# working.net
KiCad netlist of a schematic drawn in EAGLE
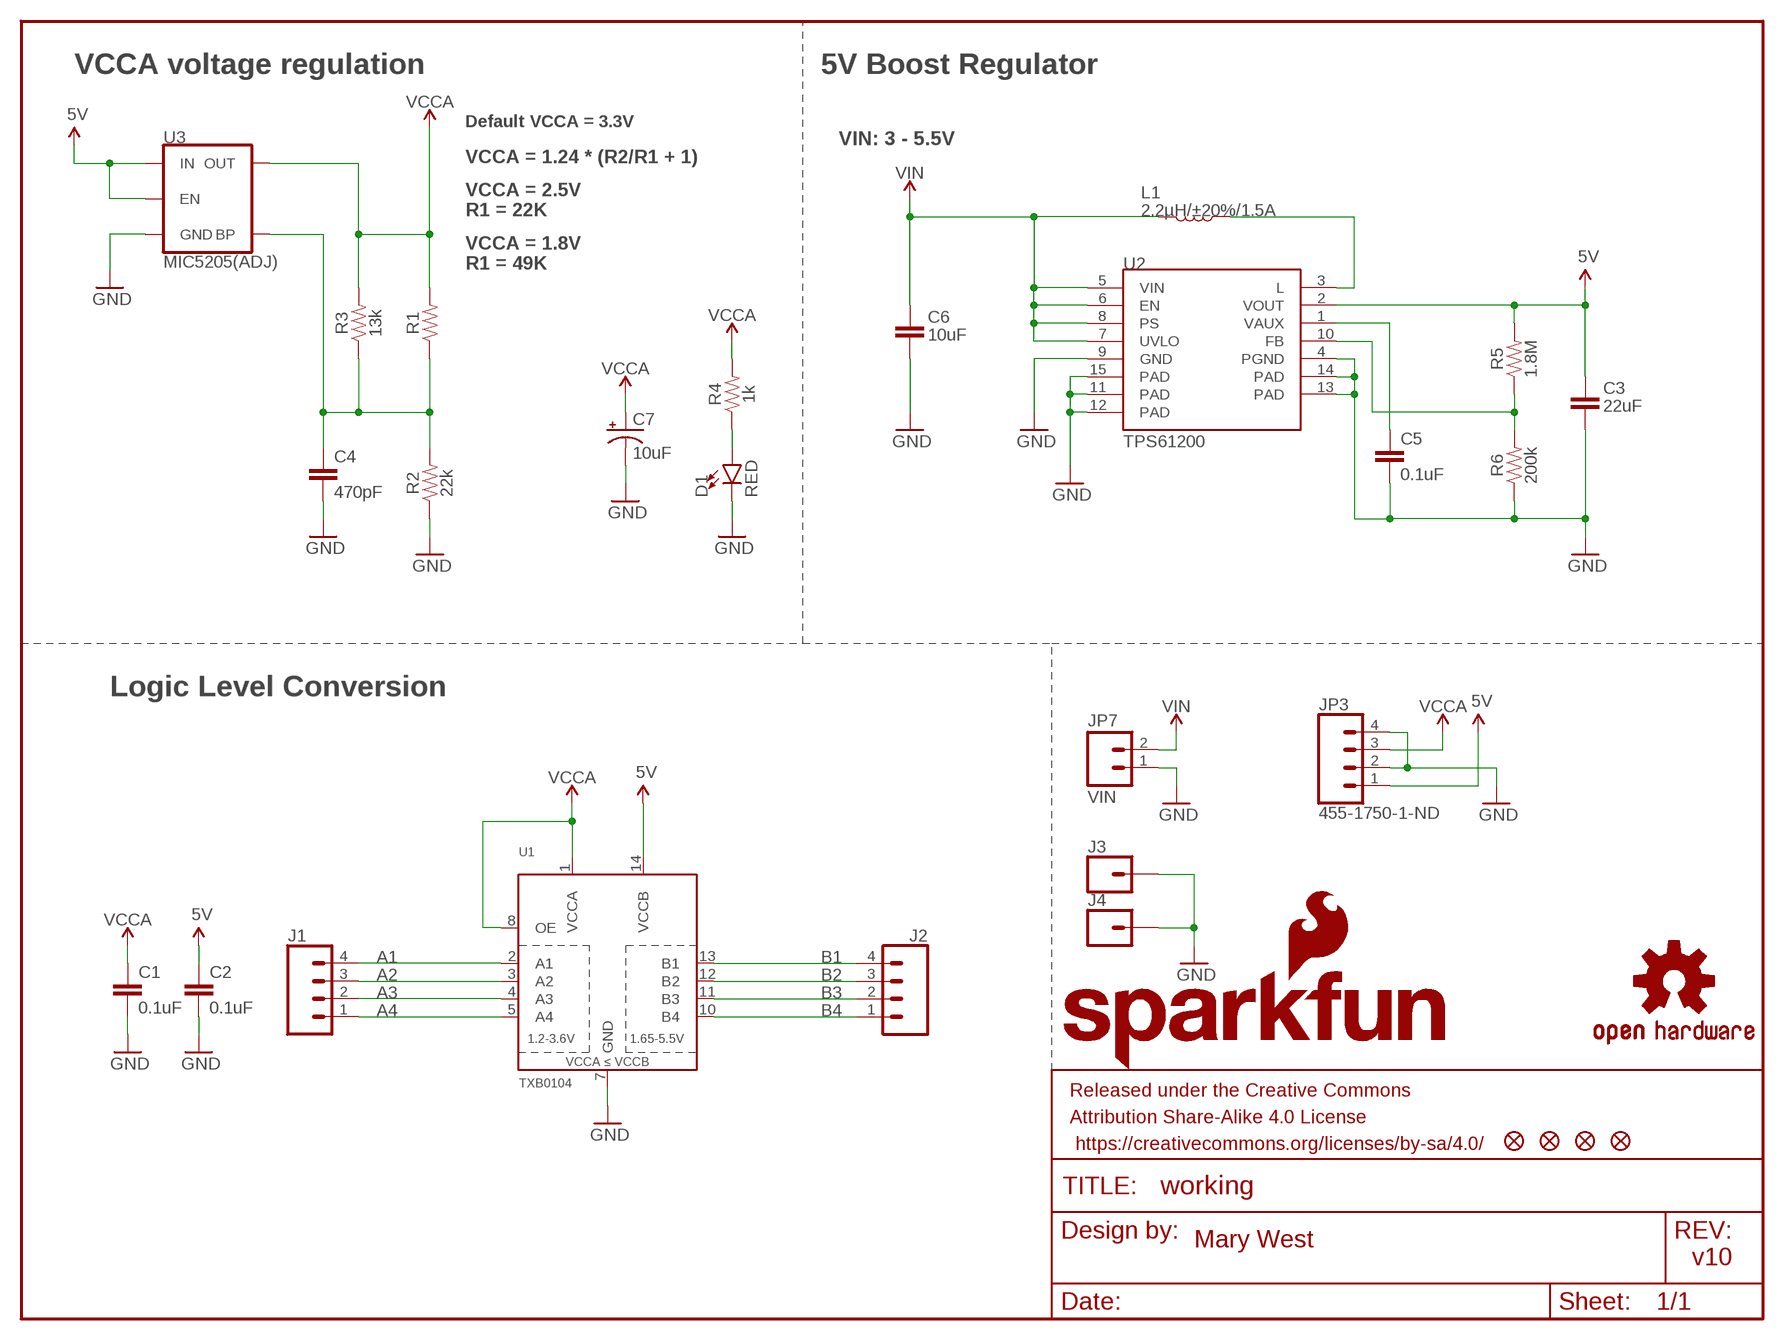
[diagram p0: schematic, sheet 1]

(export (version "E")
  (design (tool "Eeschema 10.0.6"))
  (components
    (comp (ref "C1")
      (value "0.1uF")
      (footprint "eagle-import:0603-CAP")
      (libsource (lib "eagle-import") (part "0.1UF-25V(+80/-20%)(0603)"))
    )
    (comp (ref "C2")
      (value "0.1uF")
      (footprint "eagle-import:0603-CAP")
      (libsource (lib "eagle-import") (part "0.1UF-25V(+80/-20%)(0603)"))
    )
    (comp (ref "C3")
      (value "22uF")
      (footprint "eagle-import:0805")
      (libsource (lib "eagle-import") (part "22UF-0805-6.3V-20%"))
    )
    (comp (ref "C4")
      (value "470pF")
      (footprint "eagle-import:0603")
      (libsource (lib "eagle-import") (part "470PF-0603-50V-5%"))
    )
    (comp (ref "C5")
      (value "0.1uF")
      (footprint "eagle-import:0603")
      (libsource (lib "eagle-import") (part "0.1UF-0603-25V-(+80/-20%)"))
    )
    (comp (ref "C6")
      (value "10uF")
      (footprint "eagle-import:0603")
      (libsource (lib "eagle-import") (part "10UF-0603-6.3V-20%"))
    )
    (comp (ref "C7")
      (value "10uF")
      (footprint "eagle-import:EIA3216")
      (libsource (lib "eagle-import") (part "10UF-POLAR-EIA3216-16V-10%(TANT)"))
    )
    (comp (ref "D1")
      (value "RED")
      (footprint "eagle-import:LED-0603")
      (libsource (lib "eagle-import") (part "LED-RED0603"))
    )
    (comp (ref "FD1")
      (value "FIDUCIALUFIDUCIAL")
      (footprint "eagle-import:FIDUCIAL-MICRO")
      (libsource (lib "eagle-import") (part "FIDUCIALUFIDUCIAL"))
    )
    (comp (ref "FD2")
      (value "FIDUCIALUFIDUCIAL")
      (footprint "eagle-import:FIDUCIAL-MICRO")
      (libsource (lib "eagle-import") (part "FIDUCIALUFIDUCIAL"))
    )
    (comp (ref "FD3")
      (value "FIDUCIALUFIDUCIAL")
      (footprint "eagle-import:FIDUCIAL-MICRO")
      (libsource (lib "eagle-import") (part "FIDUCIALUFIDUCIAL"))
    )
    (comp (ref "FD4")
      (value "FIDUCIALUFIDUCIAL")
      (footprint "eagle-import:FIDUCIAL-MICRO")
      (libsource (lib "eagle-import") (part "FIDUCIALUFIDUCIAL"))
    )
    (comp (ref "FRAME1")
      (value "FRAME-LETTER")
      (footprint "eagle-import:CREATIVE_COMMONS")
      (libsource (lib "eagle-import") (part "FRAME-LETTER"))
    )
    (comp (ref "J1")
      (value "CONN_04")
      (footprint "eagle-import:1X04")
      (libsource (lib "eagle-import") (part "CONN_04"))
    )
    (comp (ref "J2")
      (value "CONN_04")
      (footprint "eagle-import:1X04")
      (libsource (lib "eagle-import") (part "CONN_04"))
    )
    (comp (ref "J3")
      (value "CONN_01")
      (footprint "eagle-import:1X01")
      (libsource (lib "eagle-import") (part "CONN_01"))
    )
    (comp (ref "J4")
      (value "CONN_01")
      (footprint "eagle-import:1X01")
      (libsource (lib "eagle-import") (part "CONN_01"))
    )
    (comp (ref "JP3")
      (value "455-1750-1-ND")
      (footprint "eagle-import:1X04")
      (libsource (lib "eagle-import") (part "CONN_04"))
    )
    (comp (ref "JP7")
      (value "VIN")
      (footprint "eagle-import:1X02")
      (libsource (lib "eagle-import") (part "M02PTH"))
    )
    (comp (ref "L1")
      (value "2.2µH/±20%/1.5A")
      (footprint "eagle-import:INDUCTOR_2.2UH")
      (libsource (lib "eagle-import") (part "INDUCTOR-VLF4012AT-2.2UH"))
    )
    (comp (ref "LOGO1")
      (value "SFE_LOGO_NAME_FLAME.1_INCH")
      (footprint "eagle-import:SFE_LOGO_NAME_FLAME_.1")
      (libsource (lib "eagle-import") (part "SFE_LOGO_NAME_FLAME.1_INCH"))
    )
    (comp (ref "LOGO2")
      (value "OSHW-LOGOS")
      (footprint "eagle-import:OSHW-LOGO-S")
      (libsource (lib "eagle-import") (part "OSHW-LOGOS"))
    )
    (comp (ref "R1")
      (value "RESISTORAXIAL-0.3")
      (footprint "eagle-import:AXIAL-0.3")
      (libsource (lib "eagle-import") (part "RESISTORAXIAL-0.3"))
    )
    (comp (ref "R2")
      (value "22k")
      (footprint "eagle-import:0603")
      (libsource (lib "eagle-import") (part "22KOHM-0603-1/10W-1%"))
    )
    (comp (ref "R3")
      (value "13k")
      (footprint "eagle-import:0603")
      (libsource (lib "eagle-import") (part "13KOHM-0603-1/10W-1%"))
    )
    (comp (ref "R4")
      (value "1k")
      (footprint "eagle-import:0603")
      (libsource (lib "eagle-import") (part "1KOHM-0603-1/10W-1%"))
    )
    (comp (ref "R5")
      (value "1.8M")
      (footprint "eagle-import:0603")
      (libsource (lib "eagle-import") (part "1.8MOHM"))
    )
    (comp (ref "R6")
      (value "200k")
      (footprint "eagle-import:0603")
      (libsource (lib "eagle-import") (part "200KOHM-0603-1/10W-1%"))
    )
    (comp (ref "U1")
      (value "TXB0104")
      (footprint "eagle-import:TSSOP14")
      (libsource (lib "eagle-import") (part "TXB0104PWR"))
    )
    (comp (ref "U2")
      (value "TPS61200")
      (footprint "eagle-import:QFN-10_PAD")
      (libsource (lib "eagle-import") (part "TPS61200"))
    )
    (comp (ref "U3")
      (value "MIC5205(ADJ)")
      (footprint "eagle-import:SOT23-5")
      (libsource (lib "eagle-import") (part "V_REG_MIC5205ADJ"))
    )
  )
  (nets
    (net (code "1") (name "/A1") (class "Default")
      (node (ref "J1") (pin "4") (pinfunction "4_4") (pintype "passive"))
      (node (ref "U1") (pin "2") (pinfunction "A1_2") (pintype "bidirectional"))
    )
    (net (code "2") (name "/A2") (class "Default")
      (node (ref "J1") (pin "3") (pinfunction "3_3") (pintype "passive"))
      (node (ref "U1") (pin "3") (pinfunction "A2_3") (pintype "bidirectional"))
    )
    (net (code "3") (name "/A3") (class "Default")
      (node (ref "J1") (pin "2") (pinfunction "2_2") (pintype "passive"))
      (node (ref "U1") (pin "4") (pinfunction "A3_4") (pintype "bidirectional"))
    )
    (net (code "4") (name "/A4") (class "Default")
      (node (ref "J1") (pin "1") (pinfunction "1_1") (pintype "passive"))
      (node (ref "U1") (pin "5") (pinfunction "A4_5") (pintype "bidirectional"))
    )
    (net (code "5") (name "/B1") (class "Default")
      (node (ref "J2") (pin "4") (pinfunction "4_4") (pintype "passive"))
      (node (ref "U1") (pin "13") (pinfunction "B1_13") (pintype "bidirectional"))
    )
    (net (code "6") (name "/B2") (class "Default")
      (node (ref "J2") (pin "3") (pinfunction "3_3") (pintype "passive"))
      (node (ref "U1") (pin "12") (pinfunction "B2_12") (pintype "bidirectional"))
    )
    (net (code "7") (name "/B3") (class "Default")
      (node (ref "J2") (pin "2") (pinfunction "2_2") (pintype "passive"))
      (node (ref "U1") (pin "11") (pinfunction "B3_11") (pintype "bidirectional"))
    )
    (net (code "8") (name "/B4") (class "Default")
      (node (ref "J2") (pin "1") (pinfunction "1_1") (pintype "passive"))
      (node (ref "U1") (pin "10") (pinfunction "B4_10") (pintype "bidirectional"))
    )
    (net (code "9") (name "5V") (class "Default")
      (node (ref "C2") (pin "1") (pinfunction "1_1") (pintype "passive"))
      (node (ref "C3") (pin "1") (pinfunction "1_1") (pintype "passive"))
      (node (ref "JP3") (pin "1") (pinfunction "1_1") (pintype "passive"))
      (node (ref "R5") (pin "2") (pinfunction "2_2") (pintype "passive"))
      (node (ref "U1") (pin "14") (pinfunction "VCCB_14") (pintype "bidirectional"))
      (node (ref "U2") (pin "2") (pinfunction "VOUT_2") (pintype "passive"))
      (node (ref "U3") (pin "1") (pinfunction "IN_1") (pintype "input"))
      (node (ref "U3") (pin "3") (pinfunction "EN_3") (pintype "input"))
    )
    (net (code "10") (name "GND") (class "Default")
      (node (ref "C1") (pin "2") (pinfunction "2_2") (pintype "passive"))
      (node (ref "C2") (pin "2") (pinfunction "2_2") (pintype "passive"))
      (node (ref "C3") (pin "2") (pinfunction "2_2") (pintype "passive"))
      (node (ref "C4") (pin "2") (pinfunction "2_2") (pintype "passive"))
      (node (ref "C5") (pin "2") (pinfunction "2_2") (pintype "passive"))
      (node (ref "C6") (pin "2") (pinfunction "2_2") (pintype "passive"))
      (node (ref "C7") (pin "-") (pinfunction "-_-") (pintype "passive"))
      (node (ref "D1") (pin "C") (pinfunction "C_C") (pintype "passive"))
      (node (ref "J3") (pin "1") (pinfunction "1_1") (pintype "passive"))
      (node (ref "J4") (pin "1") (pinfunction "1_1") (pintype "passive"))
      (node (ref "JP3") (pin "2") (pinfunction "2_2") (pintype "passive"))
      (node (ref "JP3") (pin "4") (pinfunction "4_4") (pintype "passive"))
      (node (ref "JP7") (pin "1") (pinfunction "1_1") (pintype "passive"))
      (node (ref "R2") (pin "1") (pinfunction "1_1") (pintype "passive"))
      (node (ref "R6") (pin "1") (pinfunction "1_1") (pintype "passive"))
      (node (ref "U1") (pin "7") (pinfunction "GND_7") (pintype "bidirectional"))
      (node (ref "U2") (pin "11") (pinfunction "PAD_11") (pintype "power_in"))
      (node (ref "U2") (pin "12") (pinfunction "PAD_12") (pintype "power_in"))
      (node (ref "U2") (pin "13") (pinfunction "PAD_13") (pintype "power_in"))
      (node (ref "U2") (pin "14") (pinfunction "PAD_14") (pintype "power_in"))
      (node (ref "U2") (pin "15") (pinfunction "PAD_15") (pintype "power_in"))
      (node (ref "U2") (pin "4") (pinfunction "PGND_4") (pintype "power_in"))
      (node (ref "U2") (pin "9") (pinfunction "GND_9") (pintype "power_in"))
      (node (ref "U3") (pin "2") (pinfunction "GND_2") (pintype "input"))
    )
    (net (code "11") (name "Net-(D1-PadA)") (class "Default")
      (node (ref "D1") (pin "A") (pinfunction "A_A") (pintype "passive"))
      (node (ref "R4") (pin "1") (pinfunction "1_1") (pintype "passive"))
    )
    (net (code "12") (name "Net-(L1-1)") (class "Default")
      (node (ref "L1") (pin "P$1") (pinfunction "1_P$1") (pintype "passive"))
      (node (ref "U2") (pin "3") (pinfunction "L_3") (pintype "passive"))
    )
    (net (code "13") (name "Net-(R1-1)") (class "Default")
      (node (ref "C4") (pin "1") (pinfunction "1_1") (pintype "passive"))
      (node (ref "R1") (pin "P$1") (pinfunction "1_P$1") (pintype "passive"))
      (node (ref "R2") (pin "2") (pinfunction "2_2") (pintype "passive"))
      (node (ref "R3") (pin "1") (pinfunction "1_1") (pintype "passive"))
      (node (ref "U3") (pin "4") (pinfunction "BP_4") (pintype "input"))
    )
    (net (code "14") (name "Net-(U2-FB)") (class "Default")
      (node (ref "R5") (pin "1") (pinfunction "1_1") (pintype "passive"))
      (node (ref "R6") (pin "2") (pinfunction "2_2") (pintype "passive"))
      (node (ref "U2") (pin "10") (pinfunction "FB_10") (pintype "passive"))
    )
    (net (code "15") (name "Net-(U2-VAUX)") (class "Default")
      (node (ref "C5") (pin "1") (pinfunction "1_1") (pintype "passive"))
      (node (ref "U2") (pin "1") (pinfunction "VAUX_1") (pintype "passive"))
    )
    (net (code "16") (name "VCCA") (class "Default")
      (node (ref "C1") (pin "1") (pinfunction "1_1") (pintype "passive"))
      (node (ref "C7") (pin "+") (pinfunction "+_+") (pintype "passive"))
      (node (ref "JP3") (pin "3") (pinfunction "3_3") (pintype "passive"))
      (node (ref "R1") (pin "P$2") (pinfunction "2_P$2") (pintype "passive"))
      (node (ref "R3") (pin "2") (pinfunction "2_2") (pintype "passive"))
      (node (ref "R4") (pin "2") (pinfunction "2_2") (pintype "passive"))
      (node (ref "U1") (pin "1") (pinfunction "VCCA_1") (pintype "bidirectional"))
      (node (ref "U1") (pin "8") (pinfunction "OE_8") (pintype "bidirectional"))
      (node (ref "U3") (pin "5") (pinfunction "OUT_5") (pintype "passive"))
    )
    (net (code "17") (name "VIN") (class "Default")
      (node (ref "C6") (pin "1") (pinfunction "1_1") (pintype "passive"))
      (node (ref "JP7") (pin "2") (pinfunction "2_2") (pintype "passive"))
      (node (ref "L1") (pin "P$2") (pinfunction "2_P$2") (pintype "passive"))
      (node (ref "U2") (pin "5") (pinfunction "VIN_5") (pintype "power_in"))
      (node (ref "U2") (pin "6") (pinfunction "EN_6") (pintype "input"))
      (node (ref "U2") (pin "7") (pinfunction "UVLO_7") (pintype "passive"))
      (node (ref "U2") (pin "8") (pinfunction "PS_8") (pintype "input"))
    )
  )
)
